# Power_distribution_PCB.net
KiCad netlist of a schematic drawn in EAGLE
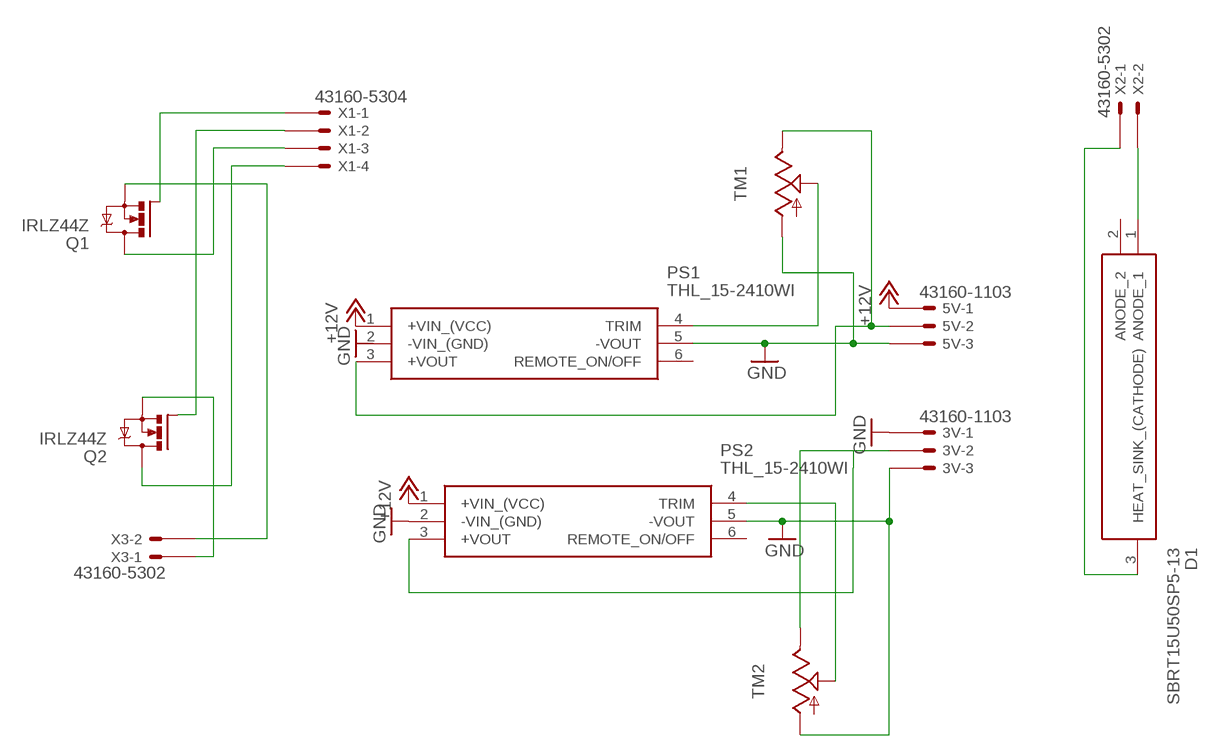
[diagram p0: schematic, sheet 1]

(export (version "E")
  (design (tool "Eeschema 10.0.6"))
  (components
    (comp (ref "3V")
      (value "43160-1103")
      (footprint "eagle-import:43160-XX03")
      (fields (field (name "MF") "MOLEX"))
      (libsource (lib "eagle-import") (part "43160-0311"))
    )
    (comp (ref "5V")
      (value "43160-1103")
      (footprint "eagle-import:43160-XX03")
      (fields (field (name "MF") "MOLEX"))
      (libsource (lib "eagle-import") (part "43160-0311"))
    )
    (comp (ref "D1")
      (value "SBRT15U50SP5-13")
      (footprint "eagle-import:POWERDI5")
      (fields (field (name "RS_PART_NUMBER") "8283301P"))
      (libsource (lib "eagle-import") (part "SBRT15U50SP5-13"))
    )
    (comp (ref "PS1")
      (value "THL_15-2410WI")
      (footprint "eagle-import:THL152410WI")
      (fields
        (field (name "MANUFACTURER_PART_NUMBER") "THL 15-2410WI")
        (field (name "MOUSER_PART_NUMBER") "495-THL15-2410WI")
      )
      (libsource (lib "eagle-import") (part "THL_15-2410WI"))
    )
    (comp (ref "PS2")
      (value "THL_15-2410WI")
      (footprint "eagle-import:THL152410WI")
      (fields
        (field (name "MANUFACTURER_PART_NUMBER") "THL 15-2410WI")
        (field (name "MOUSER_PART_NUMBER") "495-THL15-2410WI")
      )
      (libsource (lib "eagle-import") (part "THL_15-2410WI"))
    )
    (comp (ref "Q1")
      (value "IRLZ44Z")
      (footprint "eagle-import:TO220BH")
      (libsource (lib "eagle-import") (part "IRLZ44Z"))
    )
    (comp (ref "Q2")
      (value "IRLZ44Z")
      (footprint "eagle-import:TO220BH")
      (libsource (lib "eagle-import") (part "IRLZ44Z"))
    )
    (comp (ref "TM1")
      (value "TRIM")
      (footprint "eagle-import:6MM")
      (libsource (lib "eagle-import") (part "TRIM"))
    )
    (comp (ref "TM2")
      (value "TRIM")
      (footprint "eagle-import:6MM")
      (libsource (lib "eagle-import") (part "TRIM"))
    )
    (comp (ref "X1")
      (value "43160-5304")
      (footprint "eagle-import:43160-XX04")
      (fields (field (name "MF") "MOLEX"))
      (libsource (lib "eagle-import") (part "43160-0453"))
    )
    (comp (ref "X2")
      (value "43160-5302")
      (footprint "eagle-import:43160-XX02")
      (fields (field (name "MF") "MOLEX"))
      (libsource (lib "eagle-import") (part "43160-0253"))
    )
    (comp (ref "X3")
      (value "43160-5302")
      (footprint "eagle-import:43160-XX02")
      (fields (field (name "MF") "MOLEX"))
      (libsource (lib "eagle-import") (part "43160-0253"))
    )
  )
  (nets
    (net (code "1") (name "+12V") (class "Default")
      (node (ref "5V") (pin "1@1") (pinfunction "S_1@1") (pintype "passive"))
      (node (ref "PS1") (pin "1") (pinfunction "+VIN_(VCC)_1") (pintype "bidirectional"))
      (node (ref "PS2") (pin "1") (pinfunction "+VIN_(VCC)_1") (pintype "bidirectional"))
    )
    (net (code "2") (name "GND") (class "Default")
      (node (ref "3V") (pin "1@1") (pinfunction "S_1@1") (pintype "passive"))
      (node (ref "3V") (pin "3@1") (pinfunction "S_3@1") (pintype "passive"))
      (node (ref "5V") (pin "3@1") (pinfunction "S_3@1") (pintype "passive"))
      (node (ref "PS1") (pin "5") (pinfunction "-VOUT_5") (pintype "bidirectional"))
      (node (ref "PS2") (pin "2") (pinfunction "-VIN_(GND)_2") (pintype "bidirectional"))
      (node (ref "PS2") (pin "5") (pinfunction "-VOUT_5") (pintype "bidirectional"))
      (node (ref "TM1") (pin "A") (pinfunction "A_A") (pintype "passive"))
      (node (ref "TM2") (pin "A") (pinfunction "A_A") (pintype "passive"))
    )
    (net (code "3") (name "Net-(D1-ANODE_1)") (class "Default")
      (node (ref "D1") (pin "1") (pinfunction "ANODE_1_1") (pintype "bidirectional"))
      (node (ref "X2") (pin "2@1") (pinfunction "S_2@1") (pintype "passive"))
    )
    (net (code "4") (name "Net-(D1-HEAT_SINK_(CATHODE))") (class "Default")
      (node (ref "D1") (pin "3") (pinfunction "HEAT_SINK_(CATHODE)_3") (pintype "bidirectional"))
      (node (ref "X2") (pin "1@1") (pinfunction "S_1@1") (pintype "passive"))
    )
    (net (code "5") (name "Net-(PS1-+VOUT)") (class "Default")
      (node (ref "5V") (pin "2@1") (pinfunction "S_2@1") (pintype "passive"))
      (node (ref "PS1") (pin "3") (pinfunction "+VOUT_3") (pintype "bidirectional"))
      (node (ref "TM1") (pin "E") (pinfunction "E_E") (pintype "passive"))
    )
    (net (code "6") (name "Net-(PS1-TRIM)") (class "Default")
      (node (ref "PS1") (pin "4") (pinfunction "TRIM_4") (pintype "bidirectional"))
      (node (ref "TM1") (pin "S") (pinfunction "S_S") (pintype "passive"))
    )
    (net (code "7") (name "Net-(PS2-+VOUT)") (class "Default")
      (node (ref "3V") (pin "2@1") (pinfunction "S_2@1") (pintype "passive"))
      (node (ref "PS2") (pin "3") (pinfunction "+VOUT_3") (pintype "bidirectional"))
      (node (ref "TM2") (pin "E") (pinfunction "E_E") (pintype "passive"))
    )
    (net (code "8") (name "Net-(PS2-TRIM)") (class "Default")
      (node (ref "PS2") (pin "4") (pinfunction "TRIM_4") (pintype "bidirectional"))
      (node (ref "TM2") (pin "S") (pinfunction "S_S") (pintype "passive"))
    )
    (net (code "9") (name "Net-(Q1-PadD)") (class "Default")
      (node (ref "Q1") (pin "D") (pinfunction "D_D") (pintype "passive"))
      (node (ref "X1") (pin "3@1") (pinfunction "S_3@1") (pintype "passive"))
    )
    (net (code "10") (name "Net-(Q1-PadG)") (class "Default")
      (node (ref "Q1") (pin "G") (pinfunction "G_G") (pintype "passive"))
      (node (ref "X1") (pin "1@1") (pinfunction "S_1@1") (pintype "passive"))
    )
    (net (code "11") (name "Net-(Q1-PadS)") (class "Default")
      (node (ref "Q1") (pin "S") (pinfunction "S_S") (pintype "passive"))
      (node (ref "X3") (pin "2@1") (pinfunction "S_2@1") (pintype "passive"))
    )
    (net (code "12") (name "Net-(Q2-PadD)") (class "Default")
      (node (ref "Q2") (pin "D") (pinfunction "D_D") (pintype "passive"))
      (node (ref "X1") (pin "4@1") (pinfunction "S_4@1") (pintype "passive"))
    )
    (net (code "13") (name "Net-(Q2-PadG)") (class "Default")
      (node (ref "Q2") (pin "G") (pinfunction "G_G") (pintype "passive"))
      (node (ref "X1") (pin "2@1") (pinfunction "S_2@1") (pintype "passive"))
    )
    (net (code "14") (name "Net-(Q2-PadS)") (class "Default")
      (node (ref "Q2") (pin "S") (pinfunction "S_S") (pintype "passive"))
      (node (ref "X3") (pin "1@1") (pinfunction "S_1@1") (pintype "passive"))
    )
    (net (code "15") (name "unconnected-(3VA-S-Pad1@2)") (class "Default")
      (node (ref "3V") (pin "1@2") (pinfunction "S_1@2") (pintype "passive"))
    )
    (net (code "16") (name "unconnected-(3VB-S-Pad2@2)") (class "Default")
      (node (ref "3V") (pin "2@2") (pinfunction "S_2@2") (pintype "passive"))
    )
    (net (code "17") (name "unconnected-(3VC-S-Pad3@2)") (class "Default")
      (node (ref "3V") (pin "3@2") (pinfunction "S_3@2") (pintype "passive"))
    )
    (net (code "18") (name "unconnected-(5VA-S-Pad1@2)") (class "Default")
      (node (ref "5V") (pin "1@2") (pinfunction "S_1@2") (pintype "passive"))
    )
    (net (code "19") (name "unconnected-(5VB-S-Pad2@2)") (class "Default")
      (node (ref "5V") (pin "2@2") (pinfunction "S_2@2") (pintype "passive"))
    )
    (net (code "20") (name "unconnected-(5VC-S-Pad3@2)") (class "Default")
      (node (ref "5V") (pin "3@2") (pinfunction "S_3@2") (pintype "passive"))
    )
    (net (code "21") (name "unconnected-(D1-ANODE_2-Pad2)") (class "Default")
      (node (ref "D1") (pin "2") (pinfunction "ANODE_2_2") (pintype "bidirectional"))
    )
    (net (code "22") (name "unconnected-(PS1--VIN_(GND)-Pad2)") (class "Default")
      (node (ref "PS1") (pin "2") (pinfunction "-VIN_(GND)_2") (pintype "bidirectional"))
    )
    (net (code "23") (name "unconnected-(PS1-REMOTE_ON{slash}OFF-Pad6)") (class "Default")
      (node (ref "PS1") (pin "6") (pinfunction "REMOTE_ON/OFF_6") (pintype "bidirectional"))
    )
    (net (code "24") (name "unconnected-(PS2-REMOTE_ON{slash}OFF-Pad6)") (class "Default")
      (node (ref "PS2") (pin "6") (pinfunction "REMOTE_ON/OFF_6") (pintype "bidirectional"))
    )
    (net (code "25") (name "unconnected-(X1A-S-Pad1@2)") (class "Default")
      (node (ref "X1") (pin "1@2") (pinfunction "S_1@2") (pintype "passive"))
    )
    (net (code "26") (name "unconnected-(X1B-S-Pad2@2)") (class "Default")
      (node (ref "X1") (pin "2@2") (pinfunction "S_2@2") (pintype "passive"))
    )
    (net (code "27") (name "unconnected-(X1C-S-Pad3@2)") (class "Default")
      (node (ref "X1") (pin "3@2") (pinfunction "S_3@2") (pintype "passive"))
    )
    (net (code "28") (name "unconnected-(X1D-S-Pad4@2)") (class "Default")
      (node (ref "X1") (pin "4@2") (pinfunction "S_4@2") (pintype "passive"))
    )
    (net (code "29") (name "unconnected-(X2A-S-Pad1@2)") (class "Default")
      (node (ref "X2") (pin "1@2") (pinfunction "S_1@2") (pintype "passive"))
    )
    (net (code "30") (name "unconnected-(X2B-S-Pad2@2)") (class "Default")
      (node (ref "X2") (pin "2@2") (pinfunction "S_2@2") (pintype "passive"))
    )
    (net (code "31") (name "unconnected-(X3A-S-Pad1@2)") (class "Default")
      (node (ref "X3") (pin "1@2") (pinfunction "S_1@2") (pintype "passive"))
    )
    (net (code "32") (name "unconnected-(X3B-S-Pad2@2)") (class "Default")
      (node (ref "X3") (pin "2@2") (pinfunction "S_2@2") (pintype "passive"))
    )
  )
)
